# RfidReader.net
KiCad netlist of a schematic drawn in EAGLE
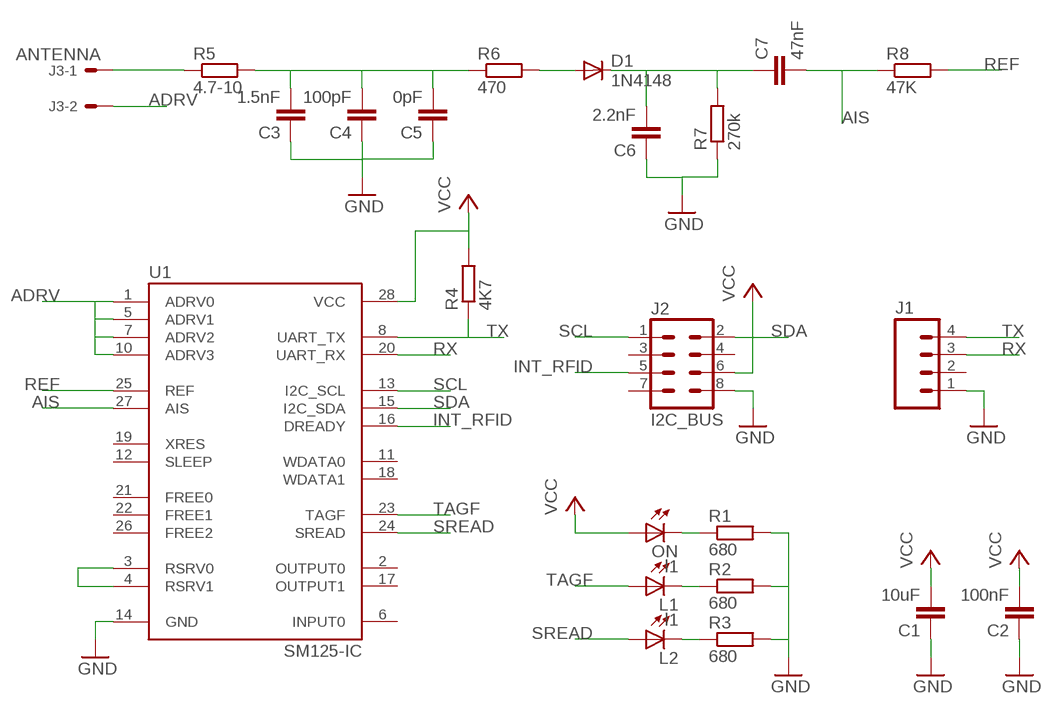
[diagram p0: schematic, sheet 1]

(export (version "E")
  (design (tool "Eeschema 10.0.6"))
  (components
    (comp (ref "C1")
      (value "10uF")
      (footprint "eagle-import:C0805")
      (libsource (lib "eagle-import") (part "C-EUC0805"))
    )
    (comp (ref "C2")
      (value "100nF")
      (footprint "eagle-import:C0805")
      (libsource (lib "eagle-import") (part "C-EUC0805"))
    )
    (comp (ref "C3")
      (value "1.5nF")
      (footprint "eagle-import:C0805")
      (libsource (lib "eagle-import") (part "C-EUC0805"))
    )
    (comp (ref "C4")
      (value "100pF")
      (footprint "eagle-import:C0805")
      (libsource (lib "eagle-import") (part "C-EUC0805"))
    )
    (comp (ref "C5")
      (value "0pF")
      (footprint "eagle-import:C0805")
      (libsource (lib "eagle-import") (part "C-EUC0805"))
    )
    (comp (ref "C6")
      (value "2.2nF")
      (footprint "eagle-import:C0805")
      (libsource (lib "eagle-import") (part "C-EUC0805"))
    )
    (comp (ref "C7")
      (value "47nF")
      (footprint "eagle-import:C0805")
      (libsource (lib "eagle-import") (part "C-EUC0805"))
    )
    (comp (ref "D1")
      (value "1N4148")
      (footprint "eagle-import:D0805")
      (libsource (lib "eagle-import") (part "1N4148"))
    )
    (comp (ref "J1")
      (value "M04PTH")
      (footprint "eagle-import:1X04")
      (libsource (lib "eagle-import") (part "M04PTH"))
    )
    (comp (ref "J2")
      (value "I2C_BUS")
      (footprint "eagle-import:SOCKET04X2_ANGLE")
      (libsource (lib "eagle-import") (part "IDC-SOCKET04X2IDC_SOCKECT04X2_ANGLE"))
    )
    (comp (ref "J3")
      (value "ANTENNA")
      (footprint "eagle-import:7395-02")
      (libsource (lib "eagle-import") (part "22-?-0205-7028"))
    )
    (comp (ref "L1")
      (value "l1")
      (footprint "eagle-import:CHIPLED_0805")
      (libsource (lib "eagle-import") (part "LEDCHIPLED_0805"))
    )
    (comp (ref "L2")
      (value "LEDCHIPLED_0805")
      (footprint "eagle-import:CHIPLED_0805")
      (libsource (lib "eagle-import") (part "LEDCHIPLED_0805"))
    )
    (comp (ref "ON")
      (value "l1")
      (footprint "eagle-import:CHIPLED_0805")
      (libsource (lib "eagle-import") (part "LEDCHIPLED_0805"))
    )
    (comp (ref "R1")
      (value "680")
      (footprint "eagle-import:M0805")
      (libsource (lib "eagle-import") (part "R-EU_M0805"))
    )
    (comp (ref "R2")
      (value "680")
      (footprint "eagle-import:M0805")
      (libsource (lib "eagle-import") (part "R-EU_M0805"))
    )
    (comp (ref "R3")
      (value "680")
      (footprint "eagle-import:M0805")
      (libsource (lib "eagle-import") (part "R-EU_M0805"))
    )
    (comp (ref "R4")
      (value "4K7")
      (footprint "eagle-import:M0805")
      (libsource (lib "eagle-import") (part "R-EU_M0805"))
    )
    (comp (ref "R5")
      (value "4.7-10")
      (footprint "eagle-import:M0805")
      (libsource (lib "eagle-import") (part "R-EU_M0805"))
    )
    (comp (ref "R6")
      (value "470")
      (footprint "eagle-import:M0805")
      (libsource (lib "eagle-import") (part "R-EU_M0805"))
    )
    (comp (ref "R7")
      (value "270k")
      (footprint "eagle-import:M0805")
      (libsource (lib "eagle-import") (part "R-EU_M0805"))
    )
    (comp (ref "R8")
      (value "47K")
      (footprint "eagle-import:M0805")
      (libsource (lib "eagle-import") (part "R-EU_M0805"))
    )
    (comp (ref "U1")
      (value "SM125-IC")
      (footprint "eagle-import:SOIC28")
      (libsource (lib "eagle-import") (part "SM125-IC"))
    )
  )
  (nets
    (net (code "1") (name "/ADRV") (class "Default")
      (node (ref "J3") (pin "2") (pinfunction "S_2") (pintype "passive"))
      (node (ref "U1") (pin "1") (pinfunction "ADRV0_1") (pintype "bidirectional"))
      (node (ref "U1") (pin "10") (pinfunction "ADRV3_10") (pintype "bidirectional"))
      (node (ref "U1") (pin "5") (pinfunction "ADRV1_5") (pintype "bidirectional"))
      (node (ref "U1") (pin "7") (pinfunction "ADRV2_7") (pintype "bidirectional"))
    )
    (net (code "2") (name "/AIS") (class "Default")
      (node (ref "C7") (pin "2") (pinfunction "2_2") (pintype "passive"))
      (node (ref "R8") (pin "1") (pinfunction "1_1") (pintype "passive"))
      (node (ref "U1") (pin "27") (pinfunction "AIS_27") (pintype "bidirectional"))
    )
    (net (code "3") (name "/INT_RFID") (class "Default")
      (node (ref "J2") (pin "5") (pinfunction "5_5") (pintype "passive"))
      (node (ref "U1") (pin "16") (pinfunction "DREADY_16") (pintype "bidirectional"))
    )
    (net (code "4") (name "/REF") (class "Default")
      (node (ref "R8") (pin "2") (pinfunction "2_2") (pintype "passive"))
      (node (ref "U1") (pin "25") (pinfunction "REF_25") (pintype "bidirectional"))
    )
    (net (code "5") (name "/RX") (class "Default")
      (node (ref "J1") (pin "3") (pinfunction "3_3") (pintype "passive"))
      (node (ref "U1") (pin "20") (pinfunction "UART_RX_20") (pintype "bidirectional"))
    )
    (net (code "6") (name "/SCL") (class "Default")
      (node (ref "J2") (pin "1") (pinfunction "1_1") (pintype "passive"))
      (node (ref "U1") (pin "13") (pinfunction "I2C_SCL_13") (pintype "bidirectional"))
    )
    (net (code "7") (name "/SDA") (class "Default")
      (node (ref "J2") (pin "2") (pinfunction "2_2") (pintype "passive"))
      (node (ref "U1") (pin "15") (pinfunction "I2C_SDA_15") (pintype "bidirectional"))
    )
    (net (code "8") (name "/SREAD") (class "Default")
      (node (ref "L2") (pin "A") (pinfunction "A_A") (pintype "passive"))
      (node (ref "U1") (pin "24") (pinfunction "SREAD_24") (pintype "bidirectional"))
    )
    (net (code "9") (name "/TAGF") (class "Default")
      (node (ref "L1") (pin "A") (pinfunction "A_A") (pintype "passive"))
      (node (ref "U1") (pin "23") (pinfunction "TAGF_23") (pintype "bidirectional"))
    )
    (net (code "10") (name "/TX") (class "Default")
      (node (ref "J1") (pin "4") (pinfunction "4_4") (pintype "passive"))
      (node (ref "R4") (pin "1") (pinfunction "1_1") (pintype "passive"))
      (node (ref "U1") (pin "8") (pinfunction "UART_TX_8") (pintype "bidirectional"))
    )
    (net (code "11") (name "GND") (class "Default")
      (node (ref "C1") (pin "1") (pinfunction "1_1") (pintype "passive"))
      (node (ref "C2") (pin "1") (pinfunction "1_1") (pintype "passive"))
      (node (ref "C3") (pin "1") (pinfunction "1_1") (pintype "passive"))
      (node (ref "C4") (pin "1") (pinfunction "1_1") (pintype "passive"))
      (node (ref "C5") (pin "1") (pinfunction "1_1") (pintype "passive"))
      (node (ref "C6") (pin "1") (pinfunction "1_1") (pintype "passive"))
      (node (ref "J1") (pin "1") (pinfunction "1_1") (pintype "passive"))
      (node (ref "J2") (pin "8") (pinfunction "8_8") (pintype "passive"))
      (node (ref "R1") (pin "2") (pinfunction "2_2") (pintype "passive"))
      (node (ref "R2") (pin "2") (pinfunction "2_2") (pintype "passive"))
      (node (ref "R3") (pin "2") (pinfunction "2_2") (pintype "passive"))
      (node (ref "R7") (pin "1") (pinfunction "1_1") (pintype "passive"))
      (node (ref "U1") (pin "14") (pinfunction "GND_14") (pintype "bidirectional"))
    )
    (net (code "12") (name "Net-(C3-Pad2)") (class "Default")
      (node (ref "C3") (pin "2") (pinfunction "2_2") (pintype "passive"))
      (node (ref "C4") (pin "2") (pinfunction "2_2") (pintype "passive"))
      (node (ref "C5") (pin "2") (pinfunction "2_2") (pintype "passive"))
      (node (ref "R5") (pin "2") (pinfunction "2_2") (pintype "passive"))
      (node (ref "R6") (pin "1") (pinfunction "1_1") (pintype "passive"))
    )
    (net (code "13") (name "Net-(C6-Pad2)") (class "Default")
      (node (ref "C6") (pin "2") (pinfunction "2_2") (pintype "passive"))
      (node (ref "C7") (pin "1") (pinfunction "1_1") (pintype "passive"))
      (node (ref "D1") (pin "C") (pinfunction "C_C") (pintype "passive"))
      (node (ref "R7") (pin "2") (pinfunction "2_2") (pintype "passive"))
    )
    (net (code "14") (name "Net-(D1-PadA)") (class "Default")
      (node (ref "D1") (pin "A") (pinfunction "A_A") (pintype "passive"))
      (node (ref "R6") (pin "2") (pinfunction "2_2") (pintype "passive"))
    )
    (net (code "15") (name "Net-(J3A-S)") (class "Default")
      (node (ref "J3") (pin "1") (pinfunction "S_1") (pintype "passive"))
      (node (ref "R5") (pin "1") (pinfunction "1_1") (pintype "passive"))
    )
    (net (code "16") (name "Net-(L1-PadC)") (class "Default")
      (node (ref "L1") (pin "C") (pinfunction "C_C") (pintype "passive"))
      (node (ref "R2") (pin "1") (pinfunction "1_1") (pintype "passive"))
    )
    (net (code "17") (name "Net-(L2-PadC)") (class "Default")
      (node (ref "L2") (pin "C") (pinfunction "C_C") (pintype "passive"))
      (node (ref "R3") (pin "1") (pinfunction "1_1") (pintype "passive"))
    )
    (net (code "18") (name "Net-(ON-PadC)") (class "Default")
      (node (ref "ON") (pin "C") (pinfunction "C_C") (pintype "passive"))
      (node (ref "R1") (pin "1") (pinfunction "1_1") (pintype "passive"))
    )
    (net (code "19") (name "Net-(U1-RSRV0)") (class "Default")
      (node (ref "U1") (pin "3") (pinfunction "RSRV0_3") (pintype "bidirectional"))
      (node (ref "U1") (pin "4") (pinfunction "RSRV1_4") (pintype "bidirectional"))
    )
    (net (code "20") (name "VCC") (class "Default")
      (node (ref "C1") (pin "2") (pinfunction "2_2") (pintype "passive"))
      (node (ref "C2") (pin "2") (pinfunction "2_2") (pintype "passive"))
      (node (ref "J2") (pin "6") (pinfunction "6_6") (pintype "passive"))
      (node (ref "ON") (pin "A") (pinfunction "A_A") (pintype "passive"))
      (node (ref "R4") (pin "2") (pinfunction "2_2") (pintype "passive"))
      (node (ref "U1") (pin "28") (pinfunction "VCC_28") (pintype "bidirectional"))
    )
    (net (code "21") (name "unconnected-(J1-Pad2)") (class "Default")
      (node (ref "J1") (pin "2") (pinfunction "2_2") (pintype "passive"))
    )
    (net (code "22") (name "unconnected-(J2-Pad3)") (class "Default")
      (node (ref "J2") (pin "3") (pinfunction "3_3") (pintype "passive"))
    )
    (net (code "23") (name "unconnected-(J2-Pad4)") (class "Default")
      (node (ref "J2") (pin "4") (pinfunction "4_4") (pintype "passive"))
    )
    (net (code "24") (name "unconnected-(J2-Pad7)") (class "Default")
      (node (ref "J2") (pin "7") (pinfunction "7_7") (pintype "passive"))
    )
    (net (code "25") (name "unconnected-(U1-FREE0-Pad21)") (class "Default")
      (node (ref "U1") (pin "21") (pinfunction "FREE0_21") (pintype "bidirectional"))
    )
    (net (code "26") (name "unconnected-(U1-FREE1-Pad22)") (class "Default")
      (node (ref "U1") (pin "22") (pinfunction "FREE1_22") (pintype "bidirectional"))
    )
    (net (code "27") (name "unconnected-(U1-FREE2-Pad26)") (class "Default")
      (node (ref "U1") (pin "26") (pinfunction "FREE2_26") (pintype "bidirectional"))
    )
    (net (code "28") (name "unconnected-(U1-INPUT0-Pad6)") (class "Default")
      (node (ref "U1") (pin "6") (pinfunction "INPUT0_6") (pintype "bidirectional"))
    )
    (net (code "29") (name "unconnected-(U1-OUTPUT0-Pad2)") (class "Default")
      (node (ref "U1") (pin "2") (pinfunction "OUTPUT0_2") (pintype "bidirectional"))
    )
    (net (code "30") (name "unconnected-(U1-OUTPUT1-Pad17)") (class "Default")
      (node (ref "U1") (pin "17") (pinfunction "OUTPUT1_17") (pintype "bidirectional"))
    )
    (net (code "31") (name "unconnected-(U1-SLEEP-Pad12)") (class "Default")
      (node (ref "U1") (pin "12") (pinfunction "SLEEP_12") (pintype "bidirectional"))
    )
    (net (code "32") (name "unconnected-(U1-WDATA0-Pad11)") (class "Default")
      (node (ref "U1") (pin "11") (pinfunction "WDATA0_11") (pintype "bidirectional"))
    )
    (net (code "33") (name "unconnected-(U1-WDATA1-Pad18)") (class "Default")
      (node (ref "U1") (pin "18") (pinfunction "WDATA1_18") (pintype "bidirectional"))
    )
    (net (code "34") (name "unconnected-(U1-XRES-Pad19)") (class "Default")
      (node (ref "U1") (pin "19") (pinfunction "XRES_19") (pintype "bidirectional"))
    )
  )
)
